# con-top-j4-1.net
KiCad netlist of a schematic drawn in Altium Designer
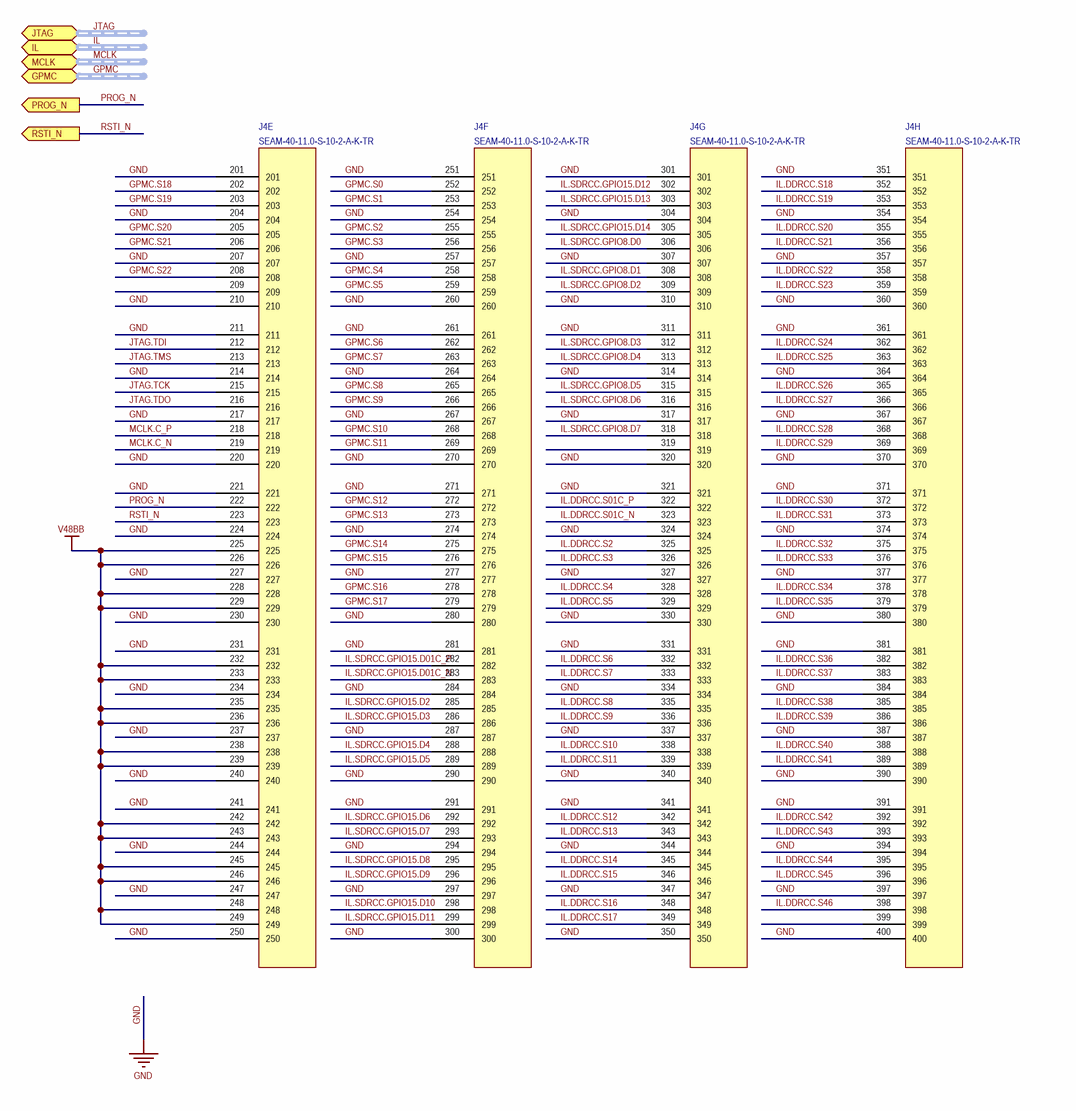
[diagram p0: con-top-j4-1.SchDoc]

(export (version "E")
  (design (tool "Eeschema 10.0.6"))
  (components
    (comp (ref "J4")
      (value "SEAM-40-11.0-S-10-2-A-K-TR")
      (footprint "samtec:SEAM-40-11.0-S-10-2-A-K-TR")
      (description "Terminal Array Assembly, Surface Mount, 0.050\" Pitch, 400 Pins")
      (fields (field (name "MANUFACTURER") "Samtec"))
      (libsource (lib "samtec") (part "SEAM-40-11.0-S-10-2-A-K-TR"))
    )
  )
  (nets
    (net (code "5") (name "/GPMC.S0") (class "Default")
      (node (ref "J4") (pin "252") (pinfunction "252_252") (pintype "passive"))
    )
    (net (code "6") (name "/GPMC.S1") (class "Default")
      (node (ref "J4") (pin "253") (pinfunction "253_253") (pintype "passive"))
    )
    (net (code "7") (name "/GPMC.S2") (class "Default")
      (node (ref "J4") (pin "255") (pinfunction "255_255") (pintype "passive"))
    )
    (net (code "8") (name "/GPMC.S3") (class "Default")
      (node (ref "J4") (pin "256") (pinfunction "256_256") (pintype "passive"))
    )
    (net (code "9") (name "/GPMC.S4") (class "Default")
      (node (ref "J4") (pin "258") (pinfunction "258_258") (pintype "passive"))
    )
    (net (code "10") (name "/GPMC.S5") (class "Default")
      (node (ref "J4") (pin "259") (pinfunction "259_259") (pintype "passive"))
    )
    (net (code "11") (name "/GPMC.S6") (class "Default")
      (node (ref "J4") (pin "262") (pinfunction "262_262") (pintype "passive"))
    )
    (net (code "12") (name "/GPMC.S7") (class "Default")
      (node (ref "J4") (pin "263") (pinfunction "263_263") (pintype "passive"))
    )
    (net (code "13") (name "/GPMC.S8") (class "Default")
      (node (ref "J4") (pin "265") (pinfunction "265_265") (pintype "passive"))
    )
    (net (code "14") (name "/GPMC.S9") (class "Default")
      (node (ref "J4") (pin "266") (pinfunction "266_266") (pintype "passive"))
    )
    (net (code "15") (name "/GPMC.S10") (class "Default")
      (node (ref "J4") (pin "268") (pinfunction "268_268") (pintype "passive"))
    )
    (net (code "16") (name "/GPMC.S11") (class "Default")
      (node (ref "J4") (pin "269") (pinfunction "269_269") (pintype "passive"))
    )
    (net (code "17") (name "/GPMC.S12") (class "Default")
      (node (ref "J4") (pin "272") (pinfunction "272_272") (pintype "passive"))
    )
    (net (code "18") (name "/GPMC.S13") (class "Default")
      (node (ref "J4") (pin "273") (pinfunction "273_273") (pintype "passive"))
    )
    (net (code "19") (name "/GPMC.S14") (class "Default")
      (node (ref "J4") (pin "275") (pinfunction "275_275") (pintype "passive"))
    )
    (net (code "20") (name "/GPMC.S15") (class "Default")
      (node (ref "J4") (pin "276") (pinfunction "276_276") (pintype "passive"))
    )
    (net (code "21") (name "/GPMC.S16") (class "Default")
      (node (ref "J4") (pin "278") (pinfunction "278_278") (pintype "passive"))
    )
    (net (code "22") (name "/GPMC.S17") (class "Default")
      (node (ref "J4") (pin "279") (pinfunction "279_279") (pintype "passive"))
    )
    (net (code "23") (name "/GPMC.S18") (class "Default")
      (node (ref "J4") (pin "202") (pinfunction "202_202") (pintype "passive"))
    )
    (net (code "24") (name "/GPMC.S19") (class "Default")
      (node (ref "J4") (pin "203") (pinfunction "203_203") (pintype "passive"))
    )
    (net (code "25") (name "/GPMC.S20") (class "Default")
      (node (ref "J4") (pin "205") (pinfunction "205_205") (pintype "passive"))
    )
    (net (code "26") (name "/GPMC.S21") (class "Default")
      (node (ref "J4") (pin "206") (pinfunction "206_206") (pintype "passive"))
    )
    (net (code "27") (name "/GPMC.S22") (class "Default")
      (node (ref "J4") (pin "208") (pinfunction "208_208") (pintype "passive"))
    )
    (net (code "28") (name "/IL.DDRCC.S01C_N") (class "Default")
      (node (ref "J4") (pin "323") (pinfunction "323_323") (pintype "passive"))
    )
    (net (code "29") (name "/IL.DDRCC.S01C_P") (class "Default")
      (node (ref "J4") (pin "322") (pinfunction "322_322") (pintype "passive"))
    )
    (net (code "30") (name "/IL.DDRCC.S2") (class "Default")
      (node (ref "J4") (pin "325") (pinfunction "325_325") (pintype "passive"))
    )
    (net (code "31") (name "/IL.DDRCC.S3") (class "Default")
      (node (ref "J4") (pin "326") (pinfunction "326_326") (pintype "passive"))
    )
    (net (code "32") (name "/IL.DDRCC.S4") (class "Default")
      (node (ref "J4") (pin "328") (pinfunction "328_328") (pintype "passive"))
    )
    (net (code "33") (name "/IL.DDRCC.S5") (class "Default")
      (node (ref "J4") (pin "329") (pinfunction "329_329") (pintype "passive"))
    )
    (net (code "34") (name "/IL.DDRCC.S6") (class "Default")
      (node (ref "J4") (pin "332") (pinfunction "332_332") (pintype "passive"))
    )
    (net (code "35") (name "/IL.DDRCC.S7") (class "Default")
      (node (ref "J4") (pin "333") (pinfunction "333_333") (pintype "passive"))
    )
    (net (code "36") (name "/IL.DDRCC.S8") (class "Default")
      (node (ref "J4") (pin "335") (pinfunction "335_335") (pintype "passive"))
    )
    (net (code "37") (name "/IL.DDRCC.S9") (class "Default")
      (node (ref "J4") (pin "336") (pinfunction "336_336") (pintype "passive"))
    )
    (net (code "38") (name "/IL.DDRCC.S10") (class "Default")
      (node (ref "J4") (pin "338") (pinfunction "338_338") (pintype "passive"))
    )
    (net (code "39") (name "/IL.DDRCC.S11") (class "Default")
      (node (ref "J4") (pin "339") (pinfunction "339_339") (pintype "passive"))
    )
    (net (code "40") (name "/IL.DDRCC.S12") (class "Default")
      (node (ref "J4") (pin "342") (pinfunction "342_342") (pintype "passive"))
    )
    (net (code "41") (name "/IL.DDRCC.S13") (class "Default")
      (node (ref "J4") (pin "343") (pinfunction "343_343") (pintype "passive"))
    )
    (net (code "42") (name "/IL.DDRCC.S14") (class "Default")
      (node (ref "J4") (pin "345") (pinfunction "345_345") (pintype "passive"))
    )
    (net (code "43") (name "/IL.DDRCC.S15") (class "Default")
      (node (ref "J4") (pin "346") (pinfunction "346_346") (pintype "passive"))
    )
    (net (code "44") (name "/IL.DDRCC.S16") (class "Default")
      (node (ref "J4") (pin "348") (pinfunction "348_348") (pintype "passive"))
    )
    (net (code "45") (name "/IL.DDRCC.S17") (class "Default")
      (node (ref "J4") (pin "349") (pinfunction "349_349") (pintype "passive"))
    )
    (net (code "46") (name "/IL.DDRCC.S18") (class "Default")
      (node (ref "J4") (pin "352") (pinfunction "352_352") (pintype "passive"))
    )
    (net (code "47") (name "/IL.DDRCC.S19") (class "Default")
      (node (ref "J4") (pin "353") (pinfunction "353_353") (pintype "passive"))
    )
    (net (code "48") (name "/IL.DDRCC.S20") (class "Default")
      (node (ref "J4") (pin "355") (pinfunction "355_355") (pintype "passive"))
    )
    (net (code "49") (name "/IL.DDRCC.S21") (class "Default")
      (node (ref "J4") (pin "356") (pinfunction "356_356") (pintype "passive"))
    )
    (net (code "50") (name "/IL.DDRCC.S22") (class "Default")
      (node (ref "J4") (pin "358") (pinfunction "358_358") (pintype "passive"))
    )
    (net (code "51") (name "/IL.DDRCC.S23") (class "Default")
      (node (ref "J4") (pin "359") (pinfunction "359_359") (pintype "passive"))
    )
    (net (code "52") (name "/IL.DDRCC.S24") (class "Default")
      (node (ref "J4") (pin "362") (pinfunction "362_362") (pintype "passive"))
    )
    (net (code "53") (name "/IL.DDRCC.S25") (class "Default")
      (node (ref "J4") (pin "363") (pinfunction "363_363") (pintype "passive"))
    )
    (net (code "54") (name "/IL.DDRCC.S26") (class "Default")
      (node (ref "J4") (pin "365") (pinfunction "365_365") (pintype "passive"))
    )
    (net (code "55") (name "/IL.DDRCC.S27") (class "Default")
      (node (ref "J4") (pin "366") (pinfunction "366_366") (pintype "passive"))
    )
    (net (code "56") (name "/IL.DDRCC.S28") (class "Default")
      (node (ref "J4") (pin "368") (pinfunction "368_368") (pintype "passive"))
    )
    (net (code "57") (name "/IL.DDRCC.S29") (class "Default")
      (node (ref "J4") (pin "369") (pinfunction "369_369") (pintype "passive"))
    )
    (net (code "58") (name "/IL.DDRCC.S30") (class "Default")
      (node (ref "J4") (pin "372") (pinfunction "372_372") (pintype "passive"))
    )
    (net (code "59") (name "/IL.DDRCC.S31") (class "Default")
      (node (ref "J4") (pin "373") (pinfunction "373_373") (pintype "passive"))
    )
    (net (code "60") (name "/IL.DDRCC.S32") (class "Default")
      (node (ref "J4") (pin "375") (pinfunction "375_375") (pintype "passive"))
    )
    (net (code "61") (name "/IL.DDRCC.S33") (class "Default")
      (node (ref "J4") (pin "376") (pinfunction "376_376") (pintype "passive"))
    )
    (net (code "62") (name "/IL.DDRCC.S34") (class "Default")
      (node (ref "J4") (pin "378") (pinfunction "378_378") (pintype "passive"))
    )
    (net (code "63") (name "/IL.DDRCC.S35") (class "Default")
      (node (ref "J4") (pin "379") (pinfunction "379_379") (pintype "passive"))
    )
    (net (code "64") (name "/IL.DDRCC.S36") (class "Default")
      (node (ref "J4") (pin "382") (pinfunction "382_382") (pintype "passive"))
    )
    (net (code "65") (name "/IL.DDRCC.S37") (class "Default")
      (node (ref "J4") (pin "383") (pinfunction "383_383") (pintype "passive"))
    )
    (net (code "66") (name "/IL.DDRCC.S38") (class "Default")
      (node (ref "J4") (pin "385") (pinfunction "385_385") (pintype "passive"))
    )
    (net (code "67") (name "/IL.DDRCC.S39") (class "Default")
      (node (ref "J4") (pin "386") (pinfunction "386_386") (pintype "passive"))
    )
    (net (code "68") (name "/IL.DDRCC.S40") (class "Default")
      (node (ref "J4") (pin "388") (pinfunction "388_388") (pintype "passive"))
    )
    (net (code "69") (name "/IL.DDRCC.S41") (class "Default")
      (node (ref "J4") (pin "389") (pinfunction "389_389") (pintype "passive"))
    )
    (net (code "70") (name "/IL.DDRCC.S42") (class "Default")
      (node (ref "J4") (pin "392") (pinfunction "392_392") (pintype "passive"))
    )
    (net (code "71") (name "/IL.DDRCC.S43") (class "Default")
      (node (ref "J4") (pin "393") (pinfunction "393_393") (pintype "passive"))
    )
    (net (code "72") (name "/IL.DDRCC.S44") (class "Default")
      (node (ref "J4") (pin "395") (pinfunction "395_395") (pintype "passive"))
    )
    (net (code "73") (name "/IL.DDRCC.S45") (class "Default")
      (node (ref "J4") (pin "396") (pinfunction "396_396") (pintype "passive"))
    )
    (net (code "74") (name "/IL.DDRCC.S46") (class "Default")
      (node (ref "J4") (pin "398") (pinfunction "398_398") (pintype "passive"))
    )
    (net (code "75") (name "/IL.SDRCC.GPIO8.D0") (class "Default")
      (node (ref "J4") (pin "306") (pinfunction "306_306") (pintype "passive"))
    )
    (net (code "76") (name "/IL.SDRCC.GPIO8.D1") (class "Default")
      (node (ref "J4") (pin "308") (pinfunction "308_308") (pintype "passive"))
    )
    (net (code "77") (name "/IL.SDRCC.GPIO8.D2") (class "Default")
      (node (ref "J4") (pin "309") (pinfunction "309_309") (pintype "passive"))
    )
    (net (code "78") (name "/IL.SDRCC.GPIO8.D3") (class "Default")
      (node (ref "J4") (pin "312") (pinfunction "312_312") (pintype "passive"))
    )
    (net (code "79") (name "/IL.SDRCC.GPIO8.D4") (class "Default")
      (node (ref "J4") (pin "313") (pinfunction "313_313") (pintype "passive"))
    )
    (net (code "80") (name "/IL.SDRCC.GPIO8.D5") (class "Default")
      (node (ref "J4") (pin "315") (pinfunction "315_315") (pintype "passive"))
    )
    (net (code "81") (name "/IL.SDRCC.GPIO8.D6") (class "Default")
      (node (ref "J4") (pin "316") (pinfunction "316_316") (pintype "passive"))
    )
    (net (code "82") (name "/IL.SDRCC.GPIO8.D7") (class "Default")
      (node (ref "J4") (pin "318") (pinfunction "318_318") (pintype "passive"))
    )
    (net (code "83") (name "/IL.SDRCC.GPIO15.D01C_N") (class "Default")
      (node (ref "J4") (pin "283") (pinfunction "283_283") (pintype "passive"))
    )
    (net (code "84") (name "/IL.SDRCC.GPIO15.D01C_P") (class "Default")
      (node (ref "J4") (pin "282") (pinfunction "282_282") (pintype "passive"))
    )
    (net (code "85") (name "/IL.SDRCC.GPIO15.D2") (class "Default")
      (node (ref "J4") (pin "285") (pinfunction "285_285") (pintype "passive"))
    )
    (net (code "86") (name "/IL.SDRCC.GPIO15.D3") (class "Default")
      (node (ref "J4") (pin "286") (pinfunction "286_286") (pintype "passive"))
    )
    (net (code "87") (name "/IL.SDRCC.GPIO15.D4") (class "Default")
      (node (ref "J4") (pin "288") (pinfunction "288_288") (pintype "passive"))
    )
    (net (code "88") (name "/IL.SDRCC.GPIO15.D5") (class "Default")
      (node (ref "J4") (pin "289") (pinfunction "289_289") (pintype "passive"))
    )
    (net (code "89") (name "/IL.SDRCC.GPIO15.D6") (class "Default")
      (node (ref "J4") (pin "292") (pinfunction "292_292") (pintype "passive"))
    )
    (net (code "90") (name "/IL.SDRCC.GPIO15.D7") (class "Default")
      (node (ref "J4") (pin "293") (pinfunction "293_293") (pintype "passive"))
    )
    (net (code "91") (name "/IL.SDRCC.GPIO15.D8") (class "Default")
      (node (ref "J4") (pin "295") (pinfunction "295_295") (pintype "passive"))
    )
    (net (code "92") (name "/IL.SDRCC.GPIO15.D9") (class "Default")
      (node (ref "J4") (pin "296") (pinfunction "296_296") (pintype "passive"))
    )
    (net (code "93") (name "/IL.SDRCC.GPIO15.D10") (class "Default")
      (node (ref "J4") (pin "298") (pinfunction "298_298") (pintype "passive"))
    )
    (net (code "94") (name "/IL.SDRCC.GPIO15.D11") (class "Default")
      (node (ref "J4") (pin "299") (pinfunction "299_299") (pintype "passive"))
    )
    (net (code "95") (name "/IL.SDRCC.GPIO15.D12") (class "Default")
      (node (ref "J4") (pin "302") (pinfunction "302_302") (pintype "passive"))
    )
    (net (code "96") (name "/IL.SDRCC.GPIO15.D13") (class "Default")
      (node (ref "J4") (pin "303") (pinfunction "303_303") (pintype "passive"))
    )
    (net (code "97") (name "/IL.SDRCC.GPIO15.D14") (class "Default")
      (node (ref "J4") (pin "305") (pinfunction "305_305") (pintype "passive"))
    )
    (net (code "98") (name "/JTAG.TCK") (class "Default")
      (node (ref "J4") (pin "215") (pinfunction "215_215") (pintype "passive"))
    )
    (net (code "99") (name "/JTAG.TDI") (class "Default")
      (node (ref "J4") (pin "212") (pinfunction "212_212") (pintype "passive"))
    )
    (net (code "100") (name "/JTAG.TDO") (class "Default")
      (node (ref "J4") (pin "216") (pinfunction "216_216") (pintype "passive"))
    )
    (net (code "101") (name "/JTAG.TMS") (class "Default")
      (node (ref "J4") (pin "213") (pinfunction "213_213") (pintype "passive"))
    )
    (net (code "102") (name "/MCLK.C_N") (class "Default")
      (node (ref "J4") (pin "219") (pinfunction "219_219") (pintype "passive"))
    )
    (net (code "103") (name "/MCLK.C_P") (class "Default")
      (node (ref "J4") (pin "218") (pinfunction "218_218") (pintype "passive"))
    )
    (net (code "104") (name "/PROG_N") (class "Default")
      (node (ref "J4") (pin "222") (pinfunction "222_222") (pintype "passive"))
    )
    (net (code "105") (name "/RSTI_N") (class "Default")
      (node (ref "J4") (pin "223") (pinfunction "223_223") (pintype "passive"))
    )
    (net (code "110") (name "GND") (class "Default")
      (node (ref "J4") (pin "201") (pinfunction "201_201") (pintype "passive"))
      (node (ref "J4") (pin "204") (pinfunction "204_204") (pintype "passive"))
      (node (ref "J4") (pin "207") (pinfunction "207_207") (pintype "passive"))
      (node (ref "J4") (pin "210") (pinfunction "210_210") (pintype "passive"))
      (node (ref "J4") (pin "211") (pinfunction "211_211") (pintype "passive"))
      (node (ref "J4") (pin "214") (pinfunction "214_214") (pintype "passive"))
      (node (ref "J4") (pin "217") (pinfunction "217_217") (pintype "passive"))
      (node (ref "J4") (pin "220") (pinfunction "220_220") (pintype "passive"))
      (node (ref "J4") (pin "221") (pinfunction "221_221") (pintype "passive"))
      (node (ref "J4") (pin "224") (pinfunction "224_224") (pintype "passive"))
      (node (ref "J4") (pin "227") (pinfunction "227_227") (pintype "passive"))
      (node (ref "J4") (pin "230") (pinfunction "230_230") (pintype "passive"))
      (node (ref "J4") (pin "231") (pinfunction "231_231") (pintype "passive"))
      (node (ref "J4") (pin "234") (pinfunction "234_234") (pintype "passive"))
      (node (ref "J4") (pin "237") (pinfunction "237_237") (pintype "passive"))
      (node (ref "J4") (pin "240") (pinfunction "240_240") (pintype "passive"))
      (node (ref "J4") (pin "241") (pinfunction "241_241") (pintype "passive"))
      (node (ref "J4") (pin "244") (pinfunction "244_244") (pintype "passive"))
      (node (ref "J4") (pin "247") (pinfunction "247_247") (pintype "passive"))
      (node (ref "J4") (pin "250") (pinfunction "250_250") (pintype "passive"))
      (node (ref "J4") (pin "251") (pinfunction "251_251") (pintype "passive"))
      (node (ref "J4") (pin "254") (pinfunction "254_254") (pintype "passive"))
      (node (ref "J4") (pin "257") (pinfunction "257_257") (pintype "passive"))
      (node (ref "J4") (pin "260") (pinfunction "260_260") (pintype "passive"))
      (node (ref "J4") (pin "261") (pinfunction "261_261") (pintype "passive"))
      (node (ref "J4") (pin "264") (pinfunction "264_264") (pintype "passive"))
      (node (ref "J4") (pin "267") (pinfunction "267_267") (pintype "passive"))
      (node (ref "J4") (pin "270") (pinfunction "270_270") (pintype "passive"))
      (node (ref "J4") (pin "271") (pinfunction "271_271") (pintype "passive"))
      (node (ref "J4") (pin "274") (pinfunction "274_274") (pintype "passive"))
      (node (ref "J4") (pin "277") (pinfunction "277_277") (pintype "passive"))
      (node (ref "J4") (pin "280") (pinfunction "280_280") (pintype "passive"))
      (node (ref "J4") (pin "281") (pinfunction "281_281") (pintype "passive"))
      (node (ref "J4") (pin "284") (pinfunction "284_284") (pintype "passive"))
      (node (ref "J4") (pin "287") (pinfunction "287_287") (pintype "passive"))
      (node (ref "J4") (pin "290") (pinfunction "290_290") (pintype "passive"))
      (node (ref "J4") (pin "291") (pinfunction "291_291") (pintype "passive"))
      (node (ref "J4") (pin "294") (pinfunction "294_294") (pintype "passive"))
      (node (ref "J4") (pin "297") (pinfunction "297_297") (pintype "passive"))
      (node (ref "J4") (pin "300") (pinfunction "300_300") (pintype "passive"))
      (node (ref "J4") (pin "301") (pinfunction "301_301") (pintype "passive"))
      (node (ref "J4") (pin "304") (pinfunction "304_304") (pintype "passive"))
      (node (ref "J4") (pin "307") (pinfunction "307_307") (pintype "passive"))
      (node (ref "J4") (pin "310") (pinfunction "310_310") (pintype "passive"))
      (node (ref "J4") (pin "311") (pinfunction "311_311") (pintype "passive"))
      (node (ref "J4") (pin "314") (pinfunction "314_314") (pintype "passive"))
      (node (ref "J4") (pin "317") (pinfunction "317_317") (pintype "passive"))
      (node (ref "J4") (pin "320") (pinfunction "320_320") (pintype "passive"))
      (node (ref "J4") (pin "321") (pinfunction "321_321") (pintype "passive"))
      (node (ref "J4") (pin "324") (pinfunction "324_324") (pintype "passive"))
      (node (ref "J4") (pin "327") (pinfunction "327_327") (pintype "passive"))
      (node (ref "J4") (pin "330") (pinfunction "330_330") (pintype "passive"))
      (node (ref "J4") (pin "331") (pinfunction "331_331") (pintype "passive"))
      (node (ref "J4") (pin "334") (pinfunction "334_334") (pintype "passive"))
      (node (ref "J4") (pin "337") (pinfunction "337_337") (pintype "passive"))
      (node (ref "J4") (pin "340") (pinfunction "340_340") (pintype "passive"))
      (node (ref "J4") (pin "341") (pinfunction "341_341") (pintype "passive"))
      (node (ref "J4") (pin "344") (pinfunction "344_344") (pintype "passive"))
      (node (ref "J4") (pin "347") (pinfunction "347_347") (pintype "passive"))
      (node (ref "J4") (pin "350") (pinfunction "350_350") (pintype "passive"))
      (node (ref "J4") (pin "351") (pinfunction "351_351") (pintype "passive"))
      (node (ref "J4") (pin "354") (pinfunction "354_354") (pintype "passive"))
      (node (ref "J4") (pin "357") (pinfunction "357_357") (pintype "passive"))
      (node (ref "J4") (pin "360") (pinfunction "360_360") (pintype "passive"))
      (node (ref "J4") (pin "361") (pinfunction "361_361") (pintype "passive"))
      (node (ref "J4") (pin "364") (pinfunction "364_364") (pintype "passive"))
      (node (ref "J4") (pin "367") (pinfunction "367_367") (pintype "passive"))
      (node (ref "J4") (pin "370") (pinfunction "370_370") (pintype "passive"))
      (node (ref "J4") (pin "371") (pinfunction "371_371") (pintype "passive"))
      (node (ref "J4") (pin "374") (pinfunction "374_374") (pintype "passive"))
      (node (ref "J4") (pin "377") (pinfunction "377_377") (pintype "passive"))
      (node (ref "J4") (pin "380") (pinfunction "380_380") (pintype "passive"))
      (node (ref "J4") (pin "381") (pinfunction "381_381") (pintype "passive"))
      (node (ref "J4") (pin "384") (pinfunction "384_384") (pintype "passive"))
      (node (ref "J4") (pin "387") (pinfunction "387_387") (pintype "passive"))
      (node (ref "J4") (pin "390") (pinfunction "390_390") (pintype "passive"))
      (node (ref "J4") (pin "391") (pinfunction "391_391") (pintype "passive"))
      (node (ref "J4") (pin "394") (pinfunction "394_394") (pintype "passive"))
      (node (ref "J4") (pin "397") (pinfunction "397_397") (pintype "passive"))
      (node (ref "J4") (pin "400") (pinfunction "400_400") (pintype "passive"))
    )
    (net (code "111") (name "V48BB") (class "Default")
      (node (ref "J4") (pin "225") (pinfunction "225_225") (pintype "passive"))
      (node (ref "J4") (pin "226") (pinfunction "226_226") (pintype "passive"))
      (node (ref "J4") (pin "228") (pinfunction "228_228") (pintype "passive"))
      (node (ref "J4") (pin "229") (pinfunction "229_229") (pintype "passive"))
      (node (ref "J4") (pin "232") (pinfunction "232_232") (pintype "passive"))
      (node (ref "J4") (pin "233") (pinfunction "233_233") (pintype "passive"))
      (node (ref "J4") (pin "235") (pinfunction "235_235") (pintype "passive"))
      (node (ref "J4") (pin "236") (pinfunction "236_236") (pintype "passive"))
      (node (ref "J4") (pin "238") (pinfunction "238_238") (pintype "passive"))
      (node (ref "J4") (pin "239") (pinfunction "239_239") (pintype "passive"))
      (node (ref "J4") (pin "242") (pinfunction "242_242") (pintype "passive"))
      (node (ref "J4") (pin "243") (pinfunction "243_243") (pintype "passive"))
      (node (ref "J4") (pin "245") (pinfunction "245_245") (pintype "passive"))
      (node (ref "J4") (pin "246") (pinfunction "246_246") (pintype "passive"))
      (node (ref "J4") (pin "248") (pinfunction "248_248") (pintype "passive"))
      (node (ref "J4") (pin "249") (pinfunction "249_249") (pintype "passive"))
    )
    (net (code "112") (name "unconnected-(J4-Pad209)") (class "Default")
      (node (ref "J4") (pin "209") (pinfunction "209_209") (pintype "passive"))
    )
    (net (code "113") (name "unconnected-(J4-Pad319)") (class "Default")
      (node (ref "J4") (pin "319") (pinfunction "319_319") (pintype "passive"))
    )
    (net (code "114") (name "unconnected-(J4-Pad399)") (class "Default")
      (node (ref "J4") (pin "399") (pinfunction "399_399") (pintype "passive"))
    )
  )
)
